# GPS.net
KiCad netlist of a schematic drawn in Altium Designer
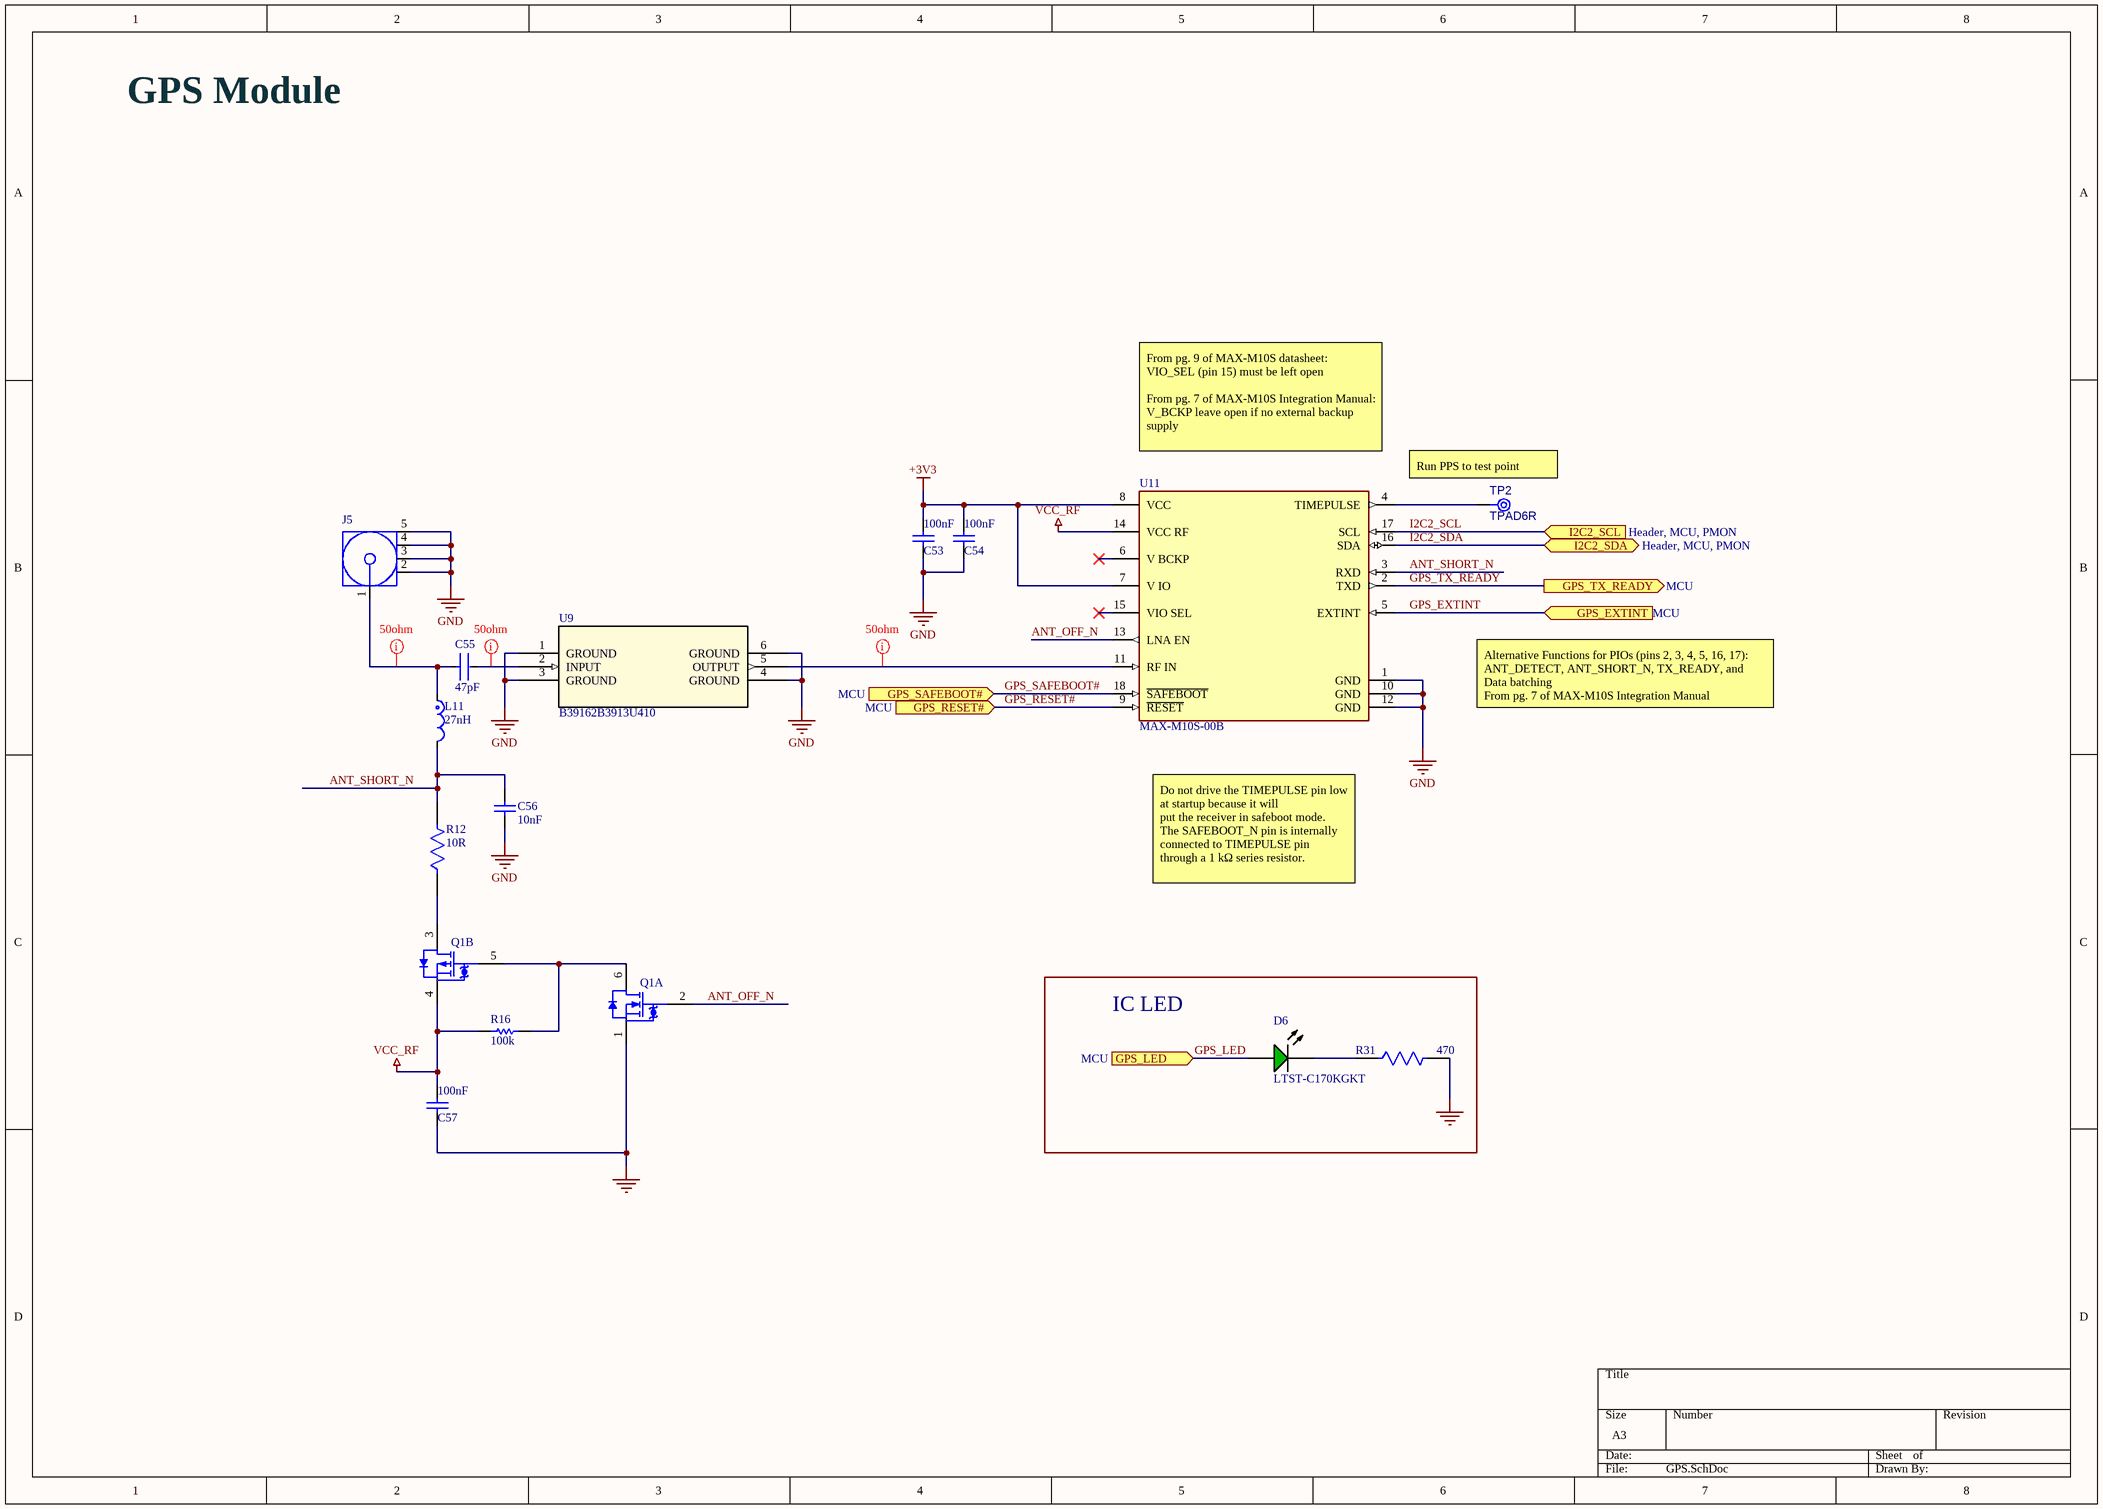
[diagram p0: GPS.SchDoc]

(export (version "E")
  (design (tool "Eeschema 10.0.6"))
  (components
    (comp (ref "C53")
      (value "100nF")
      (footprint "CAPC1005X55X25ML05T10")
      (fields (field (name "PART NUMBER") "GRM155R60J104KA01D") (field (name "MANUFACTURER") "Murata"))
      (libsource (lib "Altium Content Vault") (part "CAP"))
    )
    (comp (ref "C54")
      (value "100nF")
      (footprint "CAPC1005X55X25ML05T10")
      (fields (field (name "PART NUMBER") "GRM155R60J104KA01D") (field (name "MANUFACTURER") "Murata"))
      (libsource (lib "Altium Content Vault") (part "CAP"))
    )
    (comp (ref "C55")
      (value "47pF")
      (footprint "FP-C0402-BB-MFG")
      (description "C0402 47 pF C0G 5.00% 25 V")
      (fields
        (field (name "OCTOPART") "https://octopart.com/c0402c470j3gacauto-kemet-91893770")
        (field (name "MANUFACTURER PART NUMBER") "C0402C470J3GACAUTO")
      )
      (libsource (lib "Altium Content Vault") (part "b4654b650e69147ec39a6b967a45e02"))
    )
    (comp (ref "C56")
      (value "10nF")
      (footprint "CAPC1005X55X25LL05T10")
      (description "Chip Capacitor, 10 nF, 16 V, 10%, -55 to 125 degC, 0402 (1005 Metric), RoHS, Tape and Reel")
      (fields (field (name "MANUFACTURER") "Murata"))
      (libsource (lib "Altium Content Vault") (part "CAP-NP-2"))
    )
    (comp (ref "C57")
      (value "100nF")
      (footprint "CAPC1005X55X25ML05T10")
      (fields (field (name "PART NUMBER") "GRM155R60J104KA01D") (field (name "MANUFACTURER") "Murata"))
      (libsource (lib "Altium Content Vault") (part "CAP"))
    )
    (comp (ref "D6")
      (value "LTST-C170KGKT")
      (footprint "LTST-LTST-C170KGKT-2_V")
      (description "Ultra Bright AlInGaP Chip LED, 75 mW, -55 to 85 degC, 2-Pin SMD (0805), RoHS, Tape and Reel")
      (fields (field (name "MANUFACTURER") "Lite-On"))
      (libsource (lib "Altium Content Vault") (part "LED-GREEN-KA-2"))
    )
    (comp (ref "J5")
      (value "142-0701-801")
      (footprint "CINC-142-0701-801_V")
      (description "SMA End Launch Jack Receptacle, 50 Ohm, 0 to 18 GHz, -65 to 165 degC, 5-Pin SMD, RoHS, Bulk")
      (fields (field (name "MANUFACTURER") "EmersonConnectivitySolutions"))
      (libsource (lib "Altium Content Vault") (part "CN-S-4F-RF5"))
    )
    (comp (ref "L11")
      (value "27nH")
      (footprint "FP-LQG15HH_02-IPC_C")
      (description "Multilayer type RF Inductor 27nH ±5% 0.46Ω 350mA 0402")
      (fields (field (name "TOLERANCE") "5%"))
      (libsource (lib "Altium Content Vault") (part "4cc4b267dca4c8e51f7102f422741d8"))
    )
    (comp (ref "Q1")
      (value "NTZD3155CT1G")
      (footprint "ONSC-SOT-563-6-463A-01_V")
      (fields (field (name "MANUFACTURER") "On Semiconductor"))
      (libsource (lib "Altium Content Vault") (part "ONSC-PNMOS-6_G"))
    )
    (comp (ref "R12")
      (value "10R")
      (footprint "FP-ESR03-MFG")
      (description "10Ω ±5% 0.25W 0603 Anti-Surge Chip Resistor AEC-Q200")
      (fields (field (name "TOLERANCE") "5%"))
      (libsource (lib "Altium Content Vault") (part "1029c3af85768c4190bb7ad29bc67b5"))
    )
    (comp (ref "R16")
      (value "100k")
      (footprint "RESC1005X40X25ML10T10")
      (fields (field (name "PART NUMBER") "RK73B1ETTP104J") (field (name "MANUFACTURER") "KOA Speer"))
      (libsource (lib "Altium Content Vault") (part "RES"))
    )
    (comp (ref "R31")
      (value "470")
      (footprint "FP-CPF0603-MFG")
      (description "RES SMD 470Ω 0.1% 1/16W 0603\r\n\r\nCPF0603B470RE")
      (fields
        (field (name "MANUFACTURER") "TE Connectivity")
        (field (name "MANUFACTURER PART NUMBER") "CPF0603B470RE")
      )
      (libsource (lib "Altium Content Vault") (part "1029c3af85768c4190bb7ad29bc67b5"))
    )
    (comp (ref "TP2")
      (value "TPAD6R")
      (footprint "TP06R")
      (description "0.6mm round")
      (libsource (lib "Personal Repository") (part "CMP-001-0001-4"))
    )
    (comp (ref "U9")
      (value "B39162B3913U410")
      (footprint "B39162B3913U410_QUA")
      (description "No Description Available")
      (libsource (lib "Personal Repository") (part "B39162B3913U410"))
    )
    (comp (ref "U11")
      (value "MAX-M10S-00B")
      (footprint "FP-MAX-M10S-00B-MFG")
      (description "GNSS LCC RX, ROM, TCXO, LNA, SAW")
      (libsource (lib "Altium Content Vault") (part "a308a25f00fc71354910191737d199d"))
    )
  )
  (nets
    (net (code "1") (name "+3V3") (class "Default")
      (node (ref "C53") (pin "1") (pinfunction "1_1") (pintype "passive"))
      (node (ref "C54") (pin "1") (pinfunction "1_1") (pintype "passive"))
      (node (ref "U11") (pin "7") (pinfunction "V_IO_7") (pintype "power_in"))
      (node (ref "U11") (pin "8") (pinfunction "VCC_8") (pintype "power_in"))
    )
    (net (code "2") (name "/ANT_OFF_N") (class "Default")
      (node (ref "Q1") (pin "2") (pinfunction "G1_2") (pintype "passive"))
      (node (ref "U11") (pin "13") (pinfunction "LNA_EN_13") (pintype "output"))
    )
    (net (code "3") (name "/ANT_SHORT_N") (class "Default")
      (node (ref "C56") (pin "2") (pinfunction "2_2") (pintype "passive"))
      (node (ref "L11") (pin "2") (pinfunction "2_2") (pintype "passive"))
      (node (ref "R12") (pin "2") (pinfunction "2_2") (pintype "passive"))
      (node (ref "U11") (pin "3") (pinfunction "RXD_3") (pintype "input"))
    )
    (net (code "4") (name "/GPS_EXTINT") (class "Default")
      (node (ref "U11") (pin "5") (pinfunction "EXTINT_5") (pintype "input"))
    )
    (net (code "5") (name "/GPS_LED") (class "Default")
      (node (ref "D6") (pin "2") (pinfunction "A_2") (pintype "passive"))
    )
    (net (code "6") (name "/GPS_RESET#") (class "Default")
      (node (ref "U11") (pin "9") (pinfunction "~{RESET}_9") (pintype "input"))
    )
    (net (code "7") (name "/GPS_SAFEBOOT#") (class "Default")
      (node (ref "U11") (pin "18") (pinfunction "~{SAFEBOOT}_18") (pintype "input"))
    )
    (net (code "8") (name "/GPS_TX_READY") (class "Default")
      (node (ref "U11") (pin "2") (pinfunction "TXD_2") (pintype "output"))
    )
    (net (code "9") (name "/I2C2_SCL") (class "Default")
      (node (ref "U11") (pin "17") (pinfunction "SCL_17") (pintype "input"))
    )
    (net (code "10") (name "/I2C2_SDA") (class "Default")
      (node (ref "U11") (pin "16") (pinfunction "SDA_16") (pintype "bidirectional"))
    )
    (net (code "11") (name "GND") (class "Default")
      (node (ref "C53") (pin "2") (pinfunction "2_2") (pintype "passive"))
      (node (ref "C54") (pin "2") (pinfunction "2_2") (pintype "passive"))
      (node (ref "C56") (pin "1") (pinfunction "1_1") (pintype "passive"))
      (node (ref "C57") (pin "2") (pinfunction "2_2") (pintype "passive"))
      (node (ref "J5") (pin "2") (pinfunction "2_2") (pintype "passive"))
      (node (ref "J5") (pin "3") (pinfunction "3_3") (pintype "passive"))
      (node (ref "J5") (pin "4") (pinfunction "4_4") (pintype "passive"))
      (node (ref "J5") (pin "5") (pinfunction "5_5") (pintype "passive"))
      (node (ref "Q1") (pin "1") (pinfunction "S1_1") (pintype "passive"))
      (node (ref "R31") (pin "2") (pinfunction "2_2") (pintype "passive"))
      (node (ref "U11") (pin "1") (pinfunction "GND_1") (pintype "power_in"))
      (node (ref "U11") (pin "10") (pinfunction "GND_10") (pintype "power_in"))
      (node (ref "U11") (pin "12") (pinfunction "GND_12") (pintype "power_in"))
      (node (ref "U9") (pin "1") (pinfunction "GROUND_1") (pintype "power_in"))
      (node (ref "U9") (pin "3") (pinfunction "GROUND_3") (pintype "power_in"))
      (node (ref "U9") (pin "4") (pinfunction "GROUND_4") (pintype "power_in"))
      (node (ref "U9") (pin "6") (pinfunction "GROUND_6") (pintype "power_in"))
    )
    (net (code "12") (name "Net-(C55-Pad1)") (class "Default")
      (node (ref "C55") (pin "1") (pinfunction "1_1") (pintype "passive"))
      (node (ref "J5") (pin "1") (pinfunction "1_1") (pintype "passive"))
      (node (ref "L11") (pin "1") (pinfunction "1_1") (pintype "passive"))
    )
    (net (code "13") (name "Net-(D6-K)") (class "Default")
      (node (ref "D6") (pin "1") (pinfunction "K_1") (pintype "passive"))
      (node (ref "R31") (pin "1") (pinfunction "1_1") (pintype "passive"))
    )
    (net (code "14") (name "Net-(Q1A-D1)") (class "Default")
      (node (ref "Q1") (pin "5") (pinfunction "G2_5") (pintype "passive"))
      (node (ref "Q1") (pin "6") (pinfunction "D1_6") (pintype "passive"))
      (node (ref "R16") (pin "2") (pinfunction "2_2") (pintype "passive"))
    )
    (net (code "15") (name "Net-(Q1B-D2)") (class "Default")
      (node (ref "Q1") (pin "3") (pinfunction "D2_3") (pintype "passive"))
      (node (ref "R12") (pin "1") (pinfunction "1_1") (pintype "passive"))
    )
    (net (code "16") (name "Net-(TP2-TP)") (class "Default")
      (node (ref "TP2") (pin "1") (pinfunction "TP_1") (pintype "passive"))
      (node (ref "U11") (pin "4") (pinfunction "TIMEPULSE_4") (pintype "output"))
    )
    (net (code "17") (name "Net-(U9-INPUT)") (class "Default")
      (node (ref "C55") (pin "2") (pinfunction "2_2") (pintype "passive"))
      (node (ref "U9") (pin "2") (pinfunction "INPUT_2") (pintype "input"))
    )
    (net (code "18") (name "Net-(U11-RF_IN)") (class "Default")
      (node (ref "U11") (pin "11") (pinfunction "RF_IN_11") (pintype "input"))
      (node (ref "U9") (pin "5") (pinfunction "OUTPUT_5") (pintype "output"))
    )
    (net (code "19") (name "VCC_RF") (class "Default")
      (node (ref "C57") (pin "1") (pinfunction "1_1") (pintype "passive"))
      (node (ref "Q1") (pin "4") (pinfunction "S2_4") (pintype "passive"))
      (node (ref "R16") (pin "1") (pinfunction "1_1") (pintype "passive"))
      (node (ref "U11") (pin "14") (pinfunction "VCC_RF_14") (pintype "power_in"))
    )
    (net (code "20") (name "unconnected-(U11-VIO_SEL-Pad15)") (class "Default")
      (node (ref "U11") (pin "15") (pinfunction "VIO_SEL_15") (pintype "power_in+no_connect"))
    )
    (net (code "21") (name "unconnected-(U11-V_BCKP-Pad6)") (class "Default")
      (node (ref "U11") (pin "6") (pinfunction "V_BCKP_6") (pintype "power_in+no_connect"))
    )
  )
)
